# timer.net
KiCad netlist of a schematic drawn in EAGLE
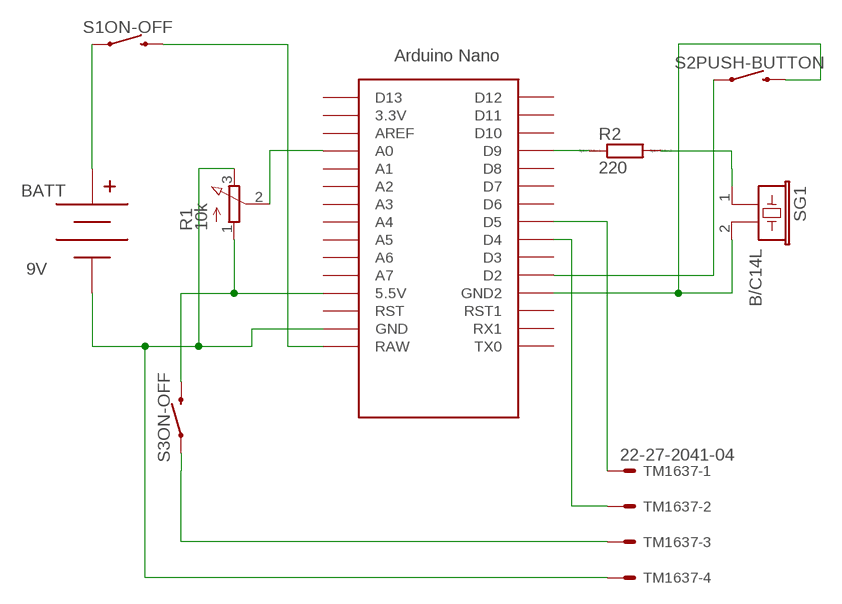
[diagram p0: schematic, sheet 1]

(export (version "E")
  (design (tool "Eeschema 10.0.6"))
  (components
    (comp (ref "BATT")
      (value "9V")
      (footprint "eagle-import:BC9VPC")
      (libsource (lib "eagle-import") (part "BC9VPC"))
    )
    (comp (ref "R1")
      (value "10k")
      (footprint "eagle-import:3RP_1610N")
      (libsource (lib "eagle-import") (part "3RP/1610N"))
    )
    (comp (ref "R2")
      (value "220")
      (footprint "eagle-import:0204_7")
      (libsource (lib "eagle-import") (part "R0204/7"))
    )
    (comp (ref "S1ON-OFF")
      (value "MOMENTARY-SWITCH-SPST-PTH-6.0MM")
      (footprint "eagle-import:TACTILE_SWITCH_PTH_6.0MM")
      (libsource (lib "eagle-import") (part "MOMENTARY-SWITCH-SPST-PTH-6.0MM"))
    )
    (comp (ref "S2PUSH-BUTTON")
      (value "MOMENTARY-SWITCH-SPST-PTH-6.0MM")
      (footprint "eagle-import:TACTILE_SWITCH_PTH_6.0MM")
      (libsource (lib "eagle-import") (part "MOMENTARY-SWITCH-SPST-PTH-6.0MM"))
    )
    (comp (ref "S3ON-OFF")
      (value "MOMENTARY-SWITCH-SPST-PTH-6.0MM")
      (footprint "eagle-import:TACTILE_SWITCH_PTH_6.0MM")
      (libsource (lib "eagle-import") (part "MOMENTARY-SWITCH-SPST-PTH-6.0MM"))
    )
    (comp (ref "SG1")
      (value "B/C14L")
      (footprint "eagle-import:B_C14L")
      (libsource (lib "eagle-import") (part "B/C14L"))
    )
    (comp (ref "TM1637")
      (value "22-27-2041-04")
      (footprint "eagle-import:6410-04")
      (fields (field (name "MF") "MOLEX"))
      (libsource (lib "eagle-import") (part "22-?-0427-2041"))
    )
    (comp (ref "U$1")
      (value "NANO")
      (footprint "eagle-import:NANO")
      (libsource (lib "eagle-import") (part "NANO"))
    )
  )
  (nets
    (net (code "1") (name "Net-(BATT-PadV+)") (class "Default")
      (node (ref "BATT") (pin "V+") (pinfunction "V+_V+") (pintype "bidirectional"))
      (node (ref "S1ON-OFF") (pin "1") (pinfunction "1_1") (pintype "passive"))
    )
    (net (code "2") (name "Net-(R1-A)") (class "Default")
      (node (ref "R1") (pin "1") (pinfunction "A_1") (pintype "passive"))
      (node (ref "S3ON-OFF") (pin "3") (pinfunction "2_3") (pintype "passive"))
      (node (ref "U$1") (pin "5V") (pinfunction "5.5V_5V") (pintype "bidirectional"))
    )
    (net (code "3") (name "Net-(R1-E)") (class "Default")
      (node (ref "BATT") (pin "V-") (pinfunction "V-_V-") (pintype "bidirectional"))
      (node (ref "R1") (pin "3") (pinfunction "E_3") (pintype "passive"))
      (node (ref "TM1637") (pin "4") (pinfunction "S_4") (pintype "passive"))
      (node (ref "U$1") (pin "GND") (pinfunction "GND_GND") (pintype "bidirectional"))
    )
    (net (code "4") (name "Net-(R1-S)") (class "Default")
      (node (ref "R1") (pin "2") (pinfunction "S_2") (pintype "passive"))
      (node (ref "U$1") (pin "A0") (pinfunction "A0_A0") (pintype "bidirectional"))
    )
    (net (code "5") (name "Net-(R2-Pad1)") (class "Default")
      (node (ref "R2") (pin "1") (pinfunction "1_1") (pintype "passive"))
      (node (ref "U$1") (pin "D9") (pinfunction "D9_D9") (pintype "bidirectional"))
    )
    (net (code "6") (name "Net-(R2-Pad2)") (class "Default")
      (node (ref "R2") (pin "2") (pinfunction "2_2") (pintype "passive"))
      (node (ref "SG1") (pin "1") (pinfunction "1_1") (pintype "passive"))
    )
    (net (code "7") (name "Net-(S1ON-OFF-2)") (class "Default")
      (node (ref "S1ON-OFF") (pin "3") (pinfunction "2_3") (pintype "passive"))
      (node (ref "U$1") (pin "RAW") (pinfunction "RAW_RAW") (pintype "bidirectional"))
    )
    (net (code "8") (name "Net-(S2PUSH-BUTTON-2)") (class "Default")
      (node (ref "S2PUSH-BUTTON") (pin "3") (pinfunction "2_3") (pintype "passive"))
      (node (ref "SG1") (pin "2") (pinfunction "2_2") (pintype "passive"))
      (node (ref "U$1") (pin "GND1") (pinfunction "GND2_GND1") (pintype "bidirectional"))
    )
    (net (code "9") (name "Net-(S2PUSH-BUTTON-Pad1)") (class "Default")
      (node (ref "S2PUSH-BUTTON") (pin "1") (pinfunction "1_1") (pintype "passive"))
      (node (ref "U$1") (pin "D2") (pinfunction "D2_D2") (pintype "bidirectional"))
    )
    (net (code "10") (name "Net-(TM1637A-S)") (class "Default")
      (node (ref "TM1637") (pin "1") (pinfunction "S_1") (pintype "passive"))
      (node (ref "U$1") (pin "D5") (pinfunction "D5_D5") (pintype "bidirectional"))
    )
    (net (code "11") (name "Net-(TM1637B-S)") (class "Default")
      (node (ref "TM1637") (pin "2") (pinfunction "S_2") (pintype "passive"))
      (node (ref "U$1") (pin "D4") (pinfunction "D4_D4") (pintype "bidirectional"))
    )
    (net (code "12") (name "Net-(TM1637C-S)") (class "Default")
      (node (ref "S3ON-OFF") (pin "1") (pinfunction "1_1") (pintype "passive"))
      (node (ref "TM1637") (pin "3") (pinfunction "S_3") (pintype "passive"))
    )
    (net (code "13") (name "unconnected-(U$1-Pad3.3V)") (class "Default")
      (node (ref "U$1") (pin "3.3V") (pinfunction "3.3V_3.3V") (pintype "bidirectional"))
    )
    (net (code "14") (name "unconnected-(U$1-PadA1)") (class "Default")
      (node (ref "U$1") (pin "A1") (pinfunction "A1_A1") (pintype "bidirectional"))
    )
    (net (code "15") (name "unconnected-(U$1-PadA2)") (class "Default")
      (node (ref "U$1") (pin "A2") (pinfunction "A2_A2") (pintype "bidirectional"))
    )
    (net (code "16") (name "unconnected-(U$1-PadA3)") (class "Default")
      (node (ref "U$1") (pin "A3") (pinfunction "A3_A3") (pintype "bidirectional"))
    )
    (net (code "17") (name "unconnected-(U$1-PadA4)") (class "Default")
      (node (ref "U$1") (pin "A4") (pinfunction "A4_A4") (pintype "bidirectional"))
    )
    (net (code "18") (name "unconnected-(U$1-PadA5)") (class "Default")
      (node (ref "U$1") (pin "A5") (pinfunction "A5_A5") (pintype "bidirectional"))
    )
    (net (code "19") (name "unconnected-(U$1-PadA6)") (class "Default")
      (node (ref "U$1") (pin "A6") (pinfunction "A6_A6") (pintype "bidirectional"))
    )
    (net (code "20") (name "unconnected-(U$1-PadA7)") (class "Default")
      (node (ref "U$1") (pin "A7") (pinfunction "A7_A7") (pintype "bidirectional"))
    )
    (net (code "21") (name "unconnected-(U$1-PadAREF)") (class "Default")
      (node (ref "U$1") (pin "AREF") (pinfunction "AREF_AREF") (pintype "bidirectional"))
    )
    (net (code "22") (name "unconnected-(U$1-PadD3)") (class "Default")
      (node (ref "U$1") (pin "D3") (pinfunction "D3_D3") (pintype "bidirectional"))
    )
    (net (code "23") (name "unconnected-(U$1-PadD6)") (class "Default")
      (node (ref "U$1") (pin "D6") (pinfunction "D6_D6") (pintype "bidirectional"))
    )
    (net (code "24") (name "unconnected-(U$1-PadD7)") (class "Default")
      (node (ref "U$1") (pin "D7") (pinfunction "D7_D7") (pintype "bidirectional"))
    )
    (net (code "25") (name "unconnected-(U$1-PadD8)") (class "Default")
      (node (ref "U$1") (pin "D8") (pinfunction "D8_D8") (pintype "bidirectional"))
    )
    (net (code "26") (name "unconnected-(U$1-PadD10)") (class "Default")
      (node (ref "U$1") (pin "D10") (pinfunction "D10_D10") (pintype "bidirectional"))
    )
    (net (code "27") (name "unconnected-(U$1-PadD11)") (class "Default")
      (node (ref "U$1") (pin "D11") (pinfunction "D11_D11") (pintype "bidirectional"))
    )
    (net (code "28") (name "unconnected-(U$1-PadD12)") (class "Default")
      (node (ref "U$1") (pin "D12") (pinfunction "D12_D12") (pintype "bidirectional"))
    )
    (net (code "29") (name "unconnected-(U$1-PadD13)") (class "Default")
      (node (ref "U$1") (pin "D13") (pinfunction "D13_D13") (pintype "bidirectional"))
    )
    (net (code "30") (name "unconnected-(U$1-PadICSP1)") (class "Default")
      (node (ref "U$1") (pin "ICSP1") (pinfunction "ICSP1_ICSP1") (pintype "bidirectional"))
    )
    (net (code "31") (name "unconnected-(U$1-PadICSP2)") (class "Default")
      (node (ref "U$1") (pin "ICSP2") (pinfunction "ICSP2_ICSP2") (pintype "bidirectional"))
    )
    (net (code "32") (name "unconnected-(U$1-PadICSP3)") (class "Default")
      (node (ref "U$1") (pin "ICSP3") (pinfunction "ICSP3_ICSP3") (pintype "bidirectional"))
    )
    (net (code "33") (name "unconnected-(U$1-PadICSP4)") (class "Default")
      (node (ref "U$1") (pin "ICSP4") (pinfunction "ICSP4_ICSP4") (pintype "bidirectional"))
    )
    (net (code "34") (name "unconnected-(U$1-PadICSP5)") (class "Default")
      (node (ref "U$1") (pin "ICSP5") (pinfunction "ICSP5_ICSP5") (pintype "bidirectional"))
    )
    (net (code "35") (name "unconnected-(U$1-PadICSP6)") (class "Default")
      (node (ref "U$1") (pin "ICSP6") (pinfunction "ICSP6_ICSP6") (pintype "bidirectional"))
    )
    (net (code "36") (name "unconnected-(U$1-PadRST)") (class "Default")
      (node (ref "U$1") (pin "RST") (pinfunction "RST_RST") (pintype "bidirectional"))
    )
    (net (code "37") (name "unconnected-(U$1-PadRST1)") (class "Default")
      (node (ref "U$1") (pin "RST1") (pinfunction "RST1_RST1") (pintype "bidirectional"))
    )
    (net (code "38") (name "unconnected-(U$1-PadRX1)") (class "Default")
      (node (ref "U$1") (pin "RX1") (pinfunction "RX1_RX1") (pintype "bidirectional"))
    )
    (net (code "39") (name "unconnected-(U$1-PadTX0)") (class "Default")
      (node (ref "U$1") (pin "TX0") (pinfunction "TX0_TX0") (pintype "bidirectional"))
    )
  )
)
